# attiny85-moisture-sensor.net
KiCad netlist of a schematic drawn in EAGLE
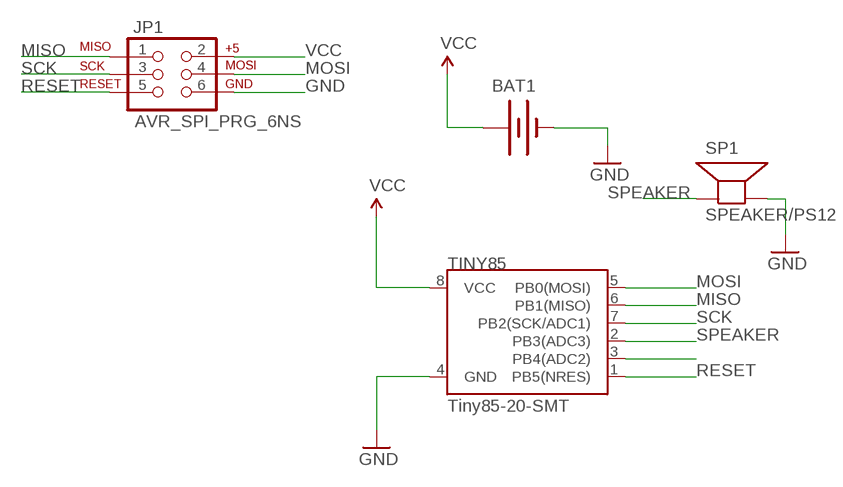
[diagram p0: schematic, sheet 1]

(export (version "E")
  (design (tool "Eeschema 10.0.6"))
  (components
    (comp (ref "BAT1")
      (value "BATTERY20SMD")
      (footprint "eagle-import:BATTCON_20MM")
      (libsource (lib "eagle-import") (part "BATTERY20SMD"))
    )
    (comp (ref "JP1")
      (value "AVR_SPI_PRG_6NS")
      (footprint "eagle-import:2X3-NS")
      (libsource (lib "eagle-import") (part "AVR_SPI_PRG_6NS"))
    )
    (comp (ref "SP1")
      (value "SPEAKER/PS12")
      (footprint "eagle-import:PS12")
      (libsource (lib "eagle-import") (part "SPEAKER/PS12"))
    )
    (comp (ref "TINY85")
      (value "Tiny85-20-SMT")
      (footprint "eagle-import:SO08-EIAJ")
      (libsource (lib "eagle-import") (part "ATTINY45TINY45-20-SMT"))
    )
  )
  (nets
    (net (code "1") (name "/MISO") (class "Default")
      (node (ref "JP1") (pin "1") (pinfunction "1_1") (pintype "passive"))
      (node (ref "TINY85") (pin "6") (pinfunction "PB1(MISO)_6") (pintype "bidirectional"))
    )
    (net (code "2") (name "/MOSI") (class "Default")
      (node (ref "JP1") (pin "4") (pinfunction "4_4") (pintype "passive"))
      (node (ref "TINY85") (pin "5") (pinfunction "PB0(MOSI)_5") (pintype "bidirectional"))
    )
    (net (code "3") (name "/RESET") (class "Default")
      (node (ref "JP1") (pin "5") (pinfunction "5_5") (pintype "passive"))
      (node (ref "TINY85") (pin "1") (pinfunction "PB5(NRES)_1") (pintype "bidirectional"))
    )
    (net (code "4") (name "/SCK") (class "Default")
      (node (ref "JP1") (pin "3") (pinfunction "3_3") (pintype "passive"))
      (node (ref "TINY85") (pin "7") (pinfunction "PB2(SCK/ADC1)_7") (pintype "bidirectional"))
    )
    (net (code "5") (name "/SPEAKER") (class "Default")
      (node (ref "SP1") (pin "P$1") (pinfunction "+_P$1") (pintype "passive"))
      (node (ref "TINY85") (pin "2") (pinfunction "PB3(ADC3)_2") (pintype "bidirectional"))
    )
    (net (code "6") (name "GND") (class "Default")
      (node (ref "BAT1") (pin "2") (pinfunction "-_2") (pintype "power_in"))
      (node (ref "JP1") (pin "6") (pinfunction "6_6") (pintype "passive"))
      (node (ref "SP1") (pin "P$2") (pinfunction "-_P$2") (pintype "passive"))
      (node (ref "TINY85") (pin "4") (pinfunction "GND_4") (pintype "bidirectional"))
    )
    (net (code "7") (name "VCC") (class "Default")
      (node (ref "BAT1") (pin "1") (pinfunction "+_1") (pintype "power_in"))
      (node (ref "JP1") (pin "2") (pinfunction "2_2") (pintype "passive"))
      (node (ref "TINY85") (pin "8") (pinfunction "VCC_8") (pintype "bidirectional"))
    )
    (net (code "8") (name "unconnected-(TINY85-PB4(ADC2)-Pad3)") (class "Default")
      (node (ref "TINY85") (pin "3") (pinfunction "PB4(ADC2)_3") (pintype "bidirectional"))
    )
  )
)
